# SpiCurrent-Old-WithShunt.net
KiCad netlist of a schematic drawn in EAGLE
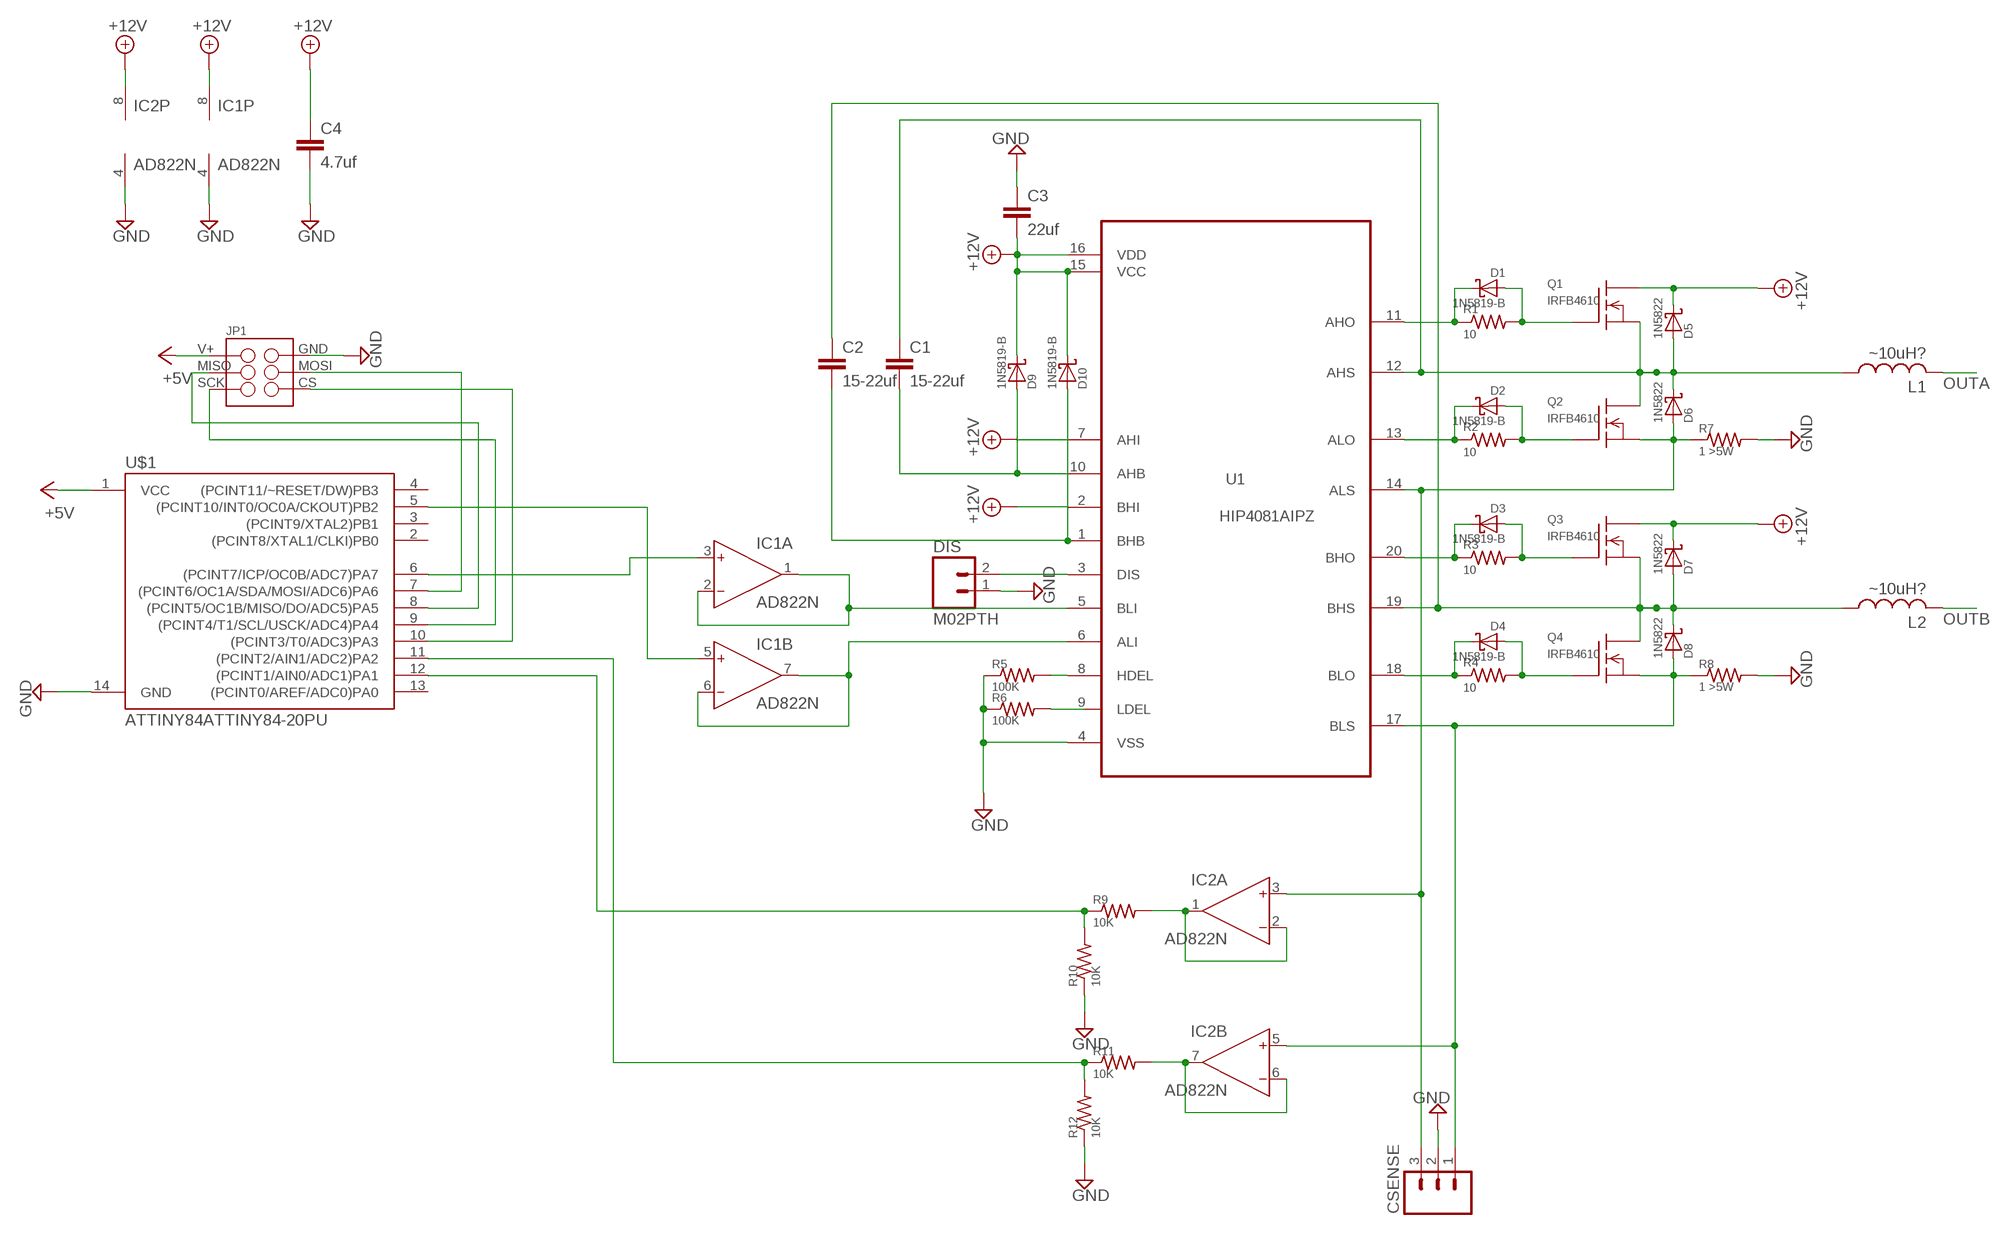
[diagram p0: schematic, sheet 1]

(export (version "E")
  (design (tool "Eeschema 10.0.6"))
  (components
    (comp (ref "C1")
      (value "15-22uf")
      (footprint "eagle-import:C050-055X075")
      (libsource (lib "eagle-import") (part "C-EU050-055X075"))
    )
    (comp (ref "C2")
      (value "15-22uf")
      (footprint "eagle-import:C050-055X075")
      (libsource (lib "eagle-import") (part "C-EU050-055X075"))
    )
    (comp (ref "C3")
      (value "22uf")
      (footprint "eagle-import:C050-055X075")
      (libsource (lib "eagle-import") (part "C-EU050-055X075"))
    )
    (comp (ref "C4")
      (value "4.7uf")
      (footprint "eagle-import:C050-055X075")
      (libsource (lib "eagle-import") (part "C-EU050-055X075"))
    )
    (comp (ref "CSENSE")
      (value "M03PTH")
      (footprint "eagle-import:1X03")
      (libsource (lib "eagle-import") (part "M03PTH"))
    )
    (comp (ref "D1")
      (value "1N5819-B")
      (footprint "eagle-import:DO41-7.6")
      (libsource (lib "eagle-import") (part "1N5819-B"))
    )
    (comp (ref "D2")
      (value "1N5819-B")
      (footprint "eagle-import:DO41-7.6")
      (libsource (lib "eagle-import") (part "1N5819-B"))
    )
    (comp (ref "D3")
      (value "1N5819-B")
      (footprint "eagle-import:DO41-7.6")
      (libsource (lib "eagle-import") (part "1N5819-B"))
    )
    (comp (ref "D4")
      (value "1N5819-B")
      (footprint "eagle-import:DO41-7.6")
      (libsource (lib "eagle-import") (part "1N5819-B"))
    )
    (comp (ref "D5")
      (value "1N5822")
      (footprint "eagle-import:DO41-7.6")
      (libsource (lib "eagle-import") (part "1N5819-B"))
    )
    (comp (ref "D6")
      (value "1N5822")
      (footprint "eagle-import:DO41-7.6")
      (libsource (lib "eagle-import") (part "1N5819-B"))
    )
    (comp (ref "D7")
      (value "1N5822")
      (footprint "eagle-import:DO41-7.6")
      (libsource (lib "eagle-import") (part "1N5819-B"))
    )
    (comp (ref "D8")
      (value "1N5822")
      (footprint "eagle-import:DO41-7.6")
      (libsource (lib "eagle-import") (part "1N5819-B"))
    )
    (comp (ref "D9")
      (value "1N5819-B")
      (footprint "eagle-import:DO41-7.6")
      (libsource (lib "eagle-import") (part "1N5819-B"))
    )
    (comp (ref "D10")
      (value "1N5819-B")
      (footprint "eagle-import:DO41-7.6")
      (libsource (lib "eagle-import") (part "1N5819-B"))
    )
    (comp (ref "DIS")
      (value "M02PTH")
      (footprint "eagle-import:1X02")
      (libsource (lib "eagle-import") (part "M02PTH"))
    )
    (comp (ref "IC1")
      (value "AD822N")
      (footprint "eagle-import:DIL08")
      (libsource (lib "eagle-import") (part "AD822N"))
    )
    (comp (ref "IC2")
      (value "AD822N")
      (footprint "eagle-import:DIL08")
      (libsource (lib "eagle-import") (part "AD822N"))
    )
    (comp (ref "JP1")
      (value "M03X2SHROUD")
      (footprint "eagle-import:2X3-SPI-SHROUDED")
      (libsource (lib "eagle-import") (part "M03X2SHROUD"))
    )
    (comp (ref "L1")
      (value "~10uH?")
      (footprint "eagle-import:TJ6-U2")
      (libsource (lib "eagle-import") (part "L-USTJ6-U2"))
    )
    (comp (ref "L2")
      (value "~10uH?")
      (footprint "eagle-import:TJ6-U2")
      (libsource (lib "eagle-import") (part "L-USTJ6-U2"))
    )
    (comp (ref "Q1")
      (value "IRFB4610")
      (footprint "eagle-import:TO220")
      (libsource (lib "eagle-import") (part "IRFB4610"))
    )
    (comp (ref "Q2")
      (value "IRFB4610")
      (footprint "eagle-import:TO220")
      (libsource (lib "eagle-import") (part "IRFB4610"))
    )
    (comp (ref "Q3")
      (value "IRFB4610")
      (footprint "eagle-import:TO220")
      (libsource (lib "eagle-import") (part "IRFB4610"))
    )
    (comp (ref "Q4")
      (value "IRFB4610")
      (footprint "eagle-import:TO220")
      (libsource (lib "eagle-import") (part "IRFB4610"))
    )
    (comp (ref "R1")
      (value "10")
      (footprint "eagle-import:0207_10")
      (libsource (lib "eagle-import") (part "R-US_0207/10"))
    )
    (comp (ref "R2")
      (value "10")
      (footprint "eagle-import:0207_10")
      (libsource (lib "eagle-import") (part "R-US_0207/10"))
    )
    (comp (ref "R3")
      (value "10")
      (footprint "eagle-import:0207_10")
      (libsource (lib "eagle-import") (part "R-US_0207/10"))
    )
    (comp (ref "R4")
      (value "10")
      (footprint "eagle-import:0207_10")
      (libsource (lib "eagle-import") (part "R-US_0207/10"))
    )
    (comp (ref "R5")
      (value "100K")
      (footprint "eagle-import:0207_10")
      (libsource (lib "eagle-import") (part "resistor-custom_R-US_0207/10"))
    )
    (comp (ref "R6")
      (value "100K")
      (footprint "eagle-import:0207_10")
      (libsource (lib "eagle-import") (part "resistor-custom_R-US_0207/10"))
    )
    (comp (ref "R7")
      (value "1 >5W")
      (footprint "eagle-import:VTA54")
      (libsource (lib "eagle-import") (part "resistor-custom_R-US_VTA54"))
    )
    (comp (ref "R8")
      (value "1 >5W")
      (footprint "eagle-import:VTA54")
      (libsource (lib "eagle-import") (part "resistor-custom_R-US_VTA54"))
    )
    (comp (ref "R9")
      (value "10K")
      (footprint "eagle-import:0207_10")
      (libsource (lib "eagle-import") (part "resistor-custom_R-US_0207/10"))
    )
    (comp (ref "R10")
      (value "10K")
      (footprint "eagle-import:0207_10")
      (libsource (lib "eagle-import") (part "resistor-custom_R-US_0207/10"))
    )
    (comp (ref "R11")
      (value "10K")
      (footprint "eagle-import:0207_10")
      (libsource (lib "eagle-import") (part "resistor-custom_R-US_0207/10"))
    )
    (comp (ref "R12")
      (value "10K")
      (footprint "eagle-import:0207_10")
      (libsource (lib "eagle-import") (part "resistor-custom_R-US_0207/10"))
    )
    (comp (ref "U$1")
      (value "ATTINY84ATTINY84-20PU")
      (footprint "eagle-import:DIL14")
      (libsource (lib "eagle-import") (part "ATTINY84ATTINY84-20PU"))
    )
    (comp (ref "U1")
      (value "HIP4081AIPZ")
      (footprint "eagle-import:DIP254P762X533-20")
      (libsource (lib "eagle-import") (part "HIP4081AIPZ"))
    )
  )
  (nets
    (net (code "1") (name "+5V") (class "Default")
      (node (ref "JP1") (pin "1") (pinfunction "1_1") (pintype "bidirectional"))
      (node (ref "U$1") (pin "1") (pinfunction "VCC_1") (pintype "bidirectional"))
    )
    (net (code "2") (name "+12V") (class "Default")
      (node (ref "C3") (pin "2") (pinfunction "2_2") (pintype "passive"))
      (node (ref "C4") (pin "1") (pinfunction "1_1") (pintype "passive"))
      (node (ref "D10") (pin "C") (pinfunction "C_C") (pintype "passive"))
      (node (ref "D5") (pin "C") (pinfunction "C_C") (pintype "passive"))
      (node (ref "D7") (pin "C") (pinfunction "C_C") (pintype "passive"))
      (node (ref "D9") (pin "C") (pinfunction "C_C") (pintype "passive"))
      (node (ref "IC1") (pin "8") (pinfunction "V+_8") (pintype "power_in"))
      (node (ref "IC2") (pin "8") (pinfunction "V+_8") (pintype "power_in"))
      (node (ref "Q1") (pin "2") (pinfunction "D_2") (pintype "passive"))
      (node (ref "Q3") (pin "2") (pinfunction "D_2") (pintype "passive"))
      (node (ref "U1") (pin "15") (pinfunction "VCC_15") (pintype "power_in"))
      (node (ref "U1") (pin "16") (pinfunction "VDD_16") (pintype "power_in"))
      (node (ref "U1") (pin "2") (pinfunction "BHI_2") (pintype "input"))
      (node (ref "U1") (pin "7") (pinfunction "AHI_7") (pintype "input"))
    )
    (net (code "3") (name "/OUTA") (class "Default")
      (node (ref "L1") (pin "2") (pinfunction "2_2") (pintype "passive"))
    )
    (net (code "4") (name "/OUTB") (class "Default")
      (node (ref "L2") (pin "2") (pinfunction "2_2") (pintype "passive"))
    )
    (net (code "5") (name "GND") (class "Default")
      (node (ref "C3") (pin "1") (pinfunction "1_1") (pintype "passive"))
      (node (ref "C4") (pin "2") (pinfunction "2_2") (pintype "passive"))
      (node (ref "CSENSE") (pin "2") (pinfunction "2_2") (pintype "passive"))
      (node (ref "DIS") (pin "1") (pinfunction "1_1") (pintype "passive"))
      (node (ref "IC1") (pin "4") (pinfunction "V-_4") (pintype "power_in"))
      (node (ref "IC2") (pin "4") (pinfunction "V-_4") (pintype "power_in"))
      (node (ref "JP1") (pin "2") (pinfunction "2_2") (pintype "bidirectional"))
      (node (ref "R10") (pin "1") (pinfunction "1_1") (pintype "passive"))
      (node (ref "R12") (pin "1") (pinfunction "1_1") (pintype "passive"))
      (node (ref "R5") (pin "1") (pinfunction "1_1") (pintype "passive"))
      (node (ref "R6") (pin "1") (pinfunction "1_1") (pintype "passive"))
      (node (ref "R7") (pin "2") (pinfunction "2_2") (pintype "passive"))
      (node (ref "R8") (pin "2") (pinfunction "2_2") (pintype "passive"))
      (node (ref "U$1") (pin "14") (pinfunction "GND_14") (pintype "bidirectional"))
      (node (ref "U1") (pin "4") (pinfunction "VSS_4") (pintype "power_in"))
    )
    (net (code "6") (name "Net-(IC1A-IN+)") (class "Default")
      (node (ref "IC1") (pin "3") (pinfunction "IN+_3") (pintype "input"))
      (node (ref "U$1") (pin "6") (pinfunction "(PCINT7/ICP/OC0B/ADC7)PA7_6") (pintype "bidirectional"))
    )
    (net (code "7") (name "Net-(IC1A-IN-)") (class "Default")
      (node (ref "IC1") (pin "1") (pinfunction "OUT_1") (pintype "output"))
      (node (ref "IC1") (pin "2") (pinfunction "IN-_2") (pintype "input"))
      (node (ref "U1") (pin "5") (pinfunction "BLI_5") (pintype "input"))
    )
    (net (code "8") (name "Net-(IC1B-IN+)") (class "Default")
      (node (ref "IC1") (pin "5") (pinfunction "IN+_5") (pintype "input"))
      (node (ref "U$1") (pin "5") (pinfunction "(PCINT10/INT0/OC0A/CKOUT)PB2_5") (pintype "bidirectional"))
    )
    (net (code "9") (name "Net-(IC1B-IN-)") (class "Default")
      (node (ref "IC1") (pin "6") (pinfunction "IN-_6") (pintype "input"))
      (node (ref "IC1") (pin "7") (pinfunction "OUT_7") (pintype "output"))
      (node (ref "U1") (pin "6") (pinfunction "ALI_6") (pintype "input"))
    )
    (net (code "10") (name "Net-(IC2A-IN+)") (class "Default")
      (node (ref "CSENSE") (pin "3") (pinfunction "3_3") (pintype "passive"))
      (node (ref "D6") (pin "A") (pinfunction "A_A") (pintype "passive"))
      (node (ref "IC2") (pin "3") (pinfunction "IN+_3") (pintype "input"))
      (node (ref "Q2") (pin "3") (pinfunction "S_3") (pintype "passive"))
      (node (ref "R7") (pin "1") (pinfunction "1_1") (pintype "passive"))
      (node (ref "U1") (pin "14") (pinfunction "ALS_14") (pintype "passive"))
    )
    (net (code "11") (name "Net-(IC2A-IN-)") (class "Default")
      (node (ref "IC2") (pin "1") (pinfunction "OUT_1") (pintype "output"))
      (node (ref "IC2") (pin "2") (pinfunction "IN-_2") (pintype "input"))
      (node (ref "R9") (pin "2") (pinfunction "2_2") (pintype "passive"))
    )
    (net (code "12") (name "Net-(IC2B-IN+)") (class "Default")
      (node (ref "CSENSE") (pin "1") (pinfunction "1_1") (pintype "passive"))
      (node (ref "D8") (pin "A") (pinfunction "A_A") (pintype "passive"))
      (node (ref "IC2") (pin "5") (pinfunction "IN+_5") (pintype "input"))
      (node (ref "Q4") (pin "3") (pinfunction "S_3") (pintype "passive"))
      (node (ref "R8") (pin "1") (pinfunction "1_1") (pintype "passive"))
      (node (ref "U1") (pin "17") (pinfunction "BLS_17") (pintype "passive"))
    )
    (net (code "13") (name "Net-(IC2B-IN-)") (class "Default")
      (node (ref "IC2") (pin "6") (pinfunction "IN-_6") (pintype "input"))
      (node (ref "IC2") (pin "7") (pinfunction "OUT_7") (pintype "output"))
      (node (ref "R11") (pin "2") (pinfunction "2_2") (pintype "passive"))
    )
    (net (code "14") (name "Net-(Q1-G)") (class "Default")
      (node (ref "D1") (pin "A") (pinfunction "A_A") (pintype "passive"))
      (node (ref "Q1") (pin "1") (pinfunction "G_1") (pintype "passive"))
      (node (ref "R1") (pin "2") (pinfunction "2_2") (pintype "passive"))
    )
    (net (code "15") (name "Net-(Q1-S)") (class "Default")
      (node (ref "C1") (pin "1") (pinfunction "1_1") (pintype "passive"))
      (node (ref "D5") (pin "A") (pinfunction "A_A") (pintype "passive"))
      (node (ref "D6") (pin "C") (pinfunction "C_C") (pintype "passive"))
      (node (ref "L1") (pin "1") (pinfunction "1_1") (pintype "passive"))
      (node (ref "Q1") (pin "3") (pinfunction "S_3") (pintype "passive"))
      (node (ref "Q2") (pin "2") (pinfunction "D_2") (pintype "passive"))
      (node (ref "U1") (pin "12") (pinfunction "AHS_12") (pintype "passive"))
    )
    (net (code "16") (name "Net-(Q2-G)") (class "Default")
      (node (ref "D2") (pin "A") (pinfunction "A_A") (pintype "passive"))
      (node (ref "Q2") (pin "1") (pinfunction "G_1") (pintype "passive"))
      (node (ref "R2") (pin "2") (pinfunction "2_2") (pintype "passive"))
    )
    (net (code "17") (name "Net-(Q3-G)") (class "Default")
      (node (ref "D3") (pin "A") (pinfunction "A_A") (pintype "passive"))
      (node (ref "Q3") (pin "1") (pinfunction "G_1") (pintype "passive"))
      (node (ref "R3") (pin "2") (pinfunction "2_2") (pintype "passive"))
    )
    (net (code "18") (name "Net-(Q3-S)") (class "Default")
      (node (ref "C2") (pin "1") (pinfunction "1_1") (pintype "passive"))
      (node (ref "D7") (pin "A") (pinfunction "A_A") (pintype "passive"))
      (node (ref "D8") (pin "C") (pinfunction "C_C") (pintype "passive"))
      (node (ref "L2") (pin "1") (pinfunction "1_1") (pintype "passive"))
      (node (ref "Q3") (pin "3") (pinfunction "S_3") (pintype "passive"))
      (node (ref "Q4") (pin "2") (pinfunction "D_2") (pintype "passive"))
      (node (ref "U1") (pin "19") (pinfunction "BHS_19") (pintype "passive"))
    )
    (net (code "19") (name "Net-(Q4-G)") (class "Default")
      (node (ref "D4") (pin "A") (pinfunction "A_A") (pintype "passive"))
      (node (ref "Q4") (pin "1") (pinfunction "G_1") (pintype "passive"))
      (node (ref "R4") (pin "2") (pinfunction "2_2") (pintype "passive"))
    )
    (net (code "20") (name "Net-(U$1-(PCINT1{slash}AIN0{slash}ADC1)PA1)") (class "Default")
      (node (ref "R10") (pin "2") (pinfunction "2_2") (pintype "passive"))
      (node (ref "R9") (pin "1") (pinfunction "1_1") (pintype "passive"))
      (node (ref "U$1") (pin "12") (pinfunction "(PCINT1/AIN0/ADC1)PA1_12") (pintype "bidirectional"))
    )
    (net (code "21") (name "Net-(U$1-(PCINT2{slash}AIN1{slash}ADC2)PA2)") (class "Default")
      (node (ref "R11") (pin "1") (pinfunction "1_1") (pintype "passive"))
      (node (ref "R12") (pin "2") (pinfunction "2_2") (pintype "passive"))
      (node (ref "U$1") (pin "11") (pinfunction "(PCINT2/AIN1/ADC2)PA2_11") (pintype "bidirectional"))
    )
    (net (code "22") (name "Net-(U$1-(PCINT3{slash}T0{slash}ADC3)PA3)") (class "Default")
      (node (ref "JP1") (pin "6") (pinfunction "6_6") (pintype "bidirectional"))
      (node (ref "U$1") (pin "10") (pinfunction "(PCINT3/T0/ADC3)PA3_10") (pintype "bidirectional"))
    )
    (net (code "23") (name "Net-(U$1-(PCINT4{slash}T1{slash}SCL{slash}USCK{slash}ADC4)PA4)") (class "Default")
      (node (ref "JP1") (pin "5") (pinfunction "5_5") (pintype "bidirectional"))
      (node (ref "U$1") (pin "9") (pinfunction "(PCINT4/T1/SCL/USCK/ADC4)PA4_9") (pintype "bidirectional"))
    )
    (net (code "24") (name "Net-(U$1-(PCINT5{slash}OC1B{slash}MISO{slash}DO{slash}ADC5)PA5)") (class "Default")
      (node (ref "JP1") (pin "3") (pinfunction "3_3") (pintype "bidirectional"))
      (node (ref "U$1") (pin "8") (pinfunction "(PCINT5/OC1B/MISO/DO/ADC5)PA5_8") (pintype "bidirectional"))
    )
    (net (code "25") (name "Net-(U$1-(PCINT6{slash}OC1A{slash}SDA{slash}MOSI{slash}ADC6)PA6)") (class "Default")
      (node (ref "JP1") (pin "4") (pinfunction "4_4") (pintype "bidirectional"))
      (node (ref "U$1") (pin "7") (pinfunction "(PCINT6/OC1A/SDA/MOSI/ADC6)PA6_7") (pintype "bidirectional"))
    )
    (net (code "26") (name "Net-(U1-AHB)") (class "Default")
      (node (ref "C1") (pin "2") (pinfunction "2_2") (pintype "passive"))
      (node (ref "D9") (pin "A") (pinfunction "A_A") (pintype "passive"))
      (node (ref "U1") (pin "10") (pinfunction "AHB_10") (pintype "input"))
    )
    (net (code "27") (name "Net-(U1-AHO)") (class "Default")
      (node (ref "D1") (pin "C") (pinfunction "C_C") (pintype "passive"))
      (node (ref "R1") (pin "1") (pinfunction "1_1") (pintype "passive"))
      (node (ref "U1") (pin "11") (pinfunction "AHO_11") (pintype "output"))
    )
    (net (code "28") (name "Net-(U1-ALO)") (class "Default")
      (node (ref "D2") (pin "C") (pinfunction "C_C") (pintype "passive"))
      (node (ref "R2") (pin "1") (pinfunction "1_1") (pintype "passive"))
      (node (ref "U1") (pin "13") (pinfunction "ALO_13") (pintype "output"))
    )
    (net (code "29") (name "Net-(U1-BHB)") (class "Default")
      (node (ref "C2") (pin "2") (pinfunction "2_2") (pintype "passive"))
      (node (ref "D10") (pin "A") (pinfunction "A_A") (pintype "passive"))
      (node (ref "U1") (pin "1") (pinfunction "BHB_1") (pintype "input"))
    )
    (net (code "30") (name "Net-(U1-BHO)") (class "Default")
      (node (ref "D3") (pin "C") (pinfunction "C_C") (pintype "passive"))
      (node (ref "R3") (pin "1") (pinfunction "1_1") (pintype "passive"))
      (node (ref "U1") (pin "20") (pinfunction "BHO_20") (pintype "output"))
    )
    (net (code "31") (name "Net-(U1-BLO)") (class "Default")
      (node (ref "D4") (pin "C") (pinfunction "C_C") (pintype "passive"))
      (node (ref "R4") (pin "1") (pinfunction "1_1") (pintype "passive"))
      (node (ref "U1") (pin "18") (pinfunction "BLO_18") (pintype "output"))
    )
    (net (code "32") (name "Net-(U1-DIS)") (class "Default")
      (node (ref "DIS") (pin "2") (pinfunction "2_2") (pintype "passive"))
      (node (ref "U1") (pin "3") (pinfunction "DIS_3") (pintype "input"))
    )
    (net (code "33") (name "Net-(U1-HDEL)") (class "Default")
      (node (ref "R5") (pin "2") (pinfunction "2_2") (pintype "passive"))
      (node (ref "U1") (pin "8") (pinfunction "HDEL_8") (pintype "input"))
    )
    (net (code "34") (name "unconnected-(R6-Pad2)") (class "Default")
      (node (ref "R6") (pin "2") (pinfunction "2_2") (pintype "passive"))
    )
    (net (code "35") (name "unconnected-(U$1-(PCINT0{slash}AREF{slash}ADC0)PA0-Pad13)") (class "Default")
      (node (ref "U$1") (pin "13") (pinfunction "(PCINT0/AREF/ADC0)PA0_13") (pintype "bidirectional"))
    )
    (net (code "36") (name "unconnected-(U$1-(PCINT8{slash}XTAL1{slash}CLKI)PB0-Pad2)") (class "Default")
      (node (ref "U$1") (pin "2") (pinfunction "(PCINT8/XTAL1/CLKI)PB0_2") (pintype "bidirectional"))
    )
    (net (code "37") (name "unconnected-(U$1-(PCINT9{slash}XTAL2)PB1-Pad3)") (class "Default")
      (node (ref "U$1") (pin "3") (pinfunction "(PCINT9/XTAL2)PB1_3") (pintype "bidirectional"))
    )
    (net (code "38") (name "unconnected-(U$1-(PCINT11{slash}~{RESET{slash}DW})PB3-Pad4)") (class "Default")
      (node (ref "U$1") (pin "4") (pinfunction "(PCINT11/~{RESET/DW})PB3_4") (pintype "bidirectional"))
    )
    (net (code "39") (name "unconnected-(U1-LDEL-Pad9)") (class "Default")
      (node (ref "U1") (pin "9") (pinfunction "LDEL_9") (pintype "input"))
    )
  )
)
